# POWER.net
KiCad netlist of a schematic drawn in Altium Designer
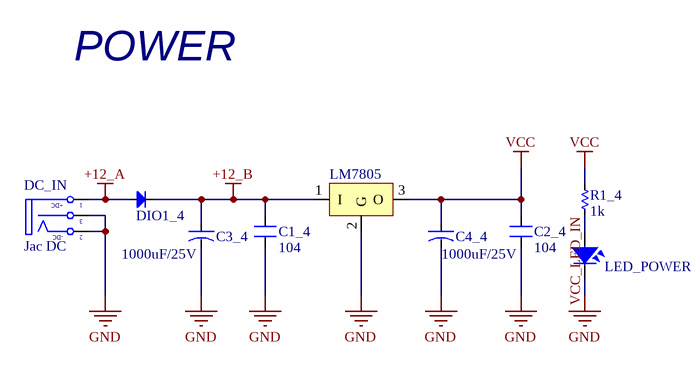
[diagram p0: POWER.SchDoc]

(export (version "E")
  (design (tool "Eeschema 10.0.6"))
  (components
    (comp (ref "C1_4") (value "104") (footprint "CN-SMD-0805") (libsource (lib "Altium Library") (part "CN")))
    (comp (ref "C2_4") (value "104") (footprint "CN-SMD-0805") (libsource (lib "Altium Library") (part "CN")))
    (comp (ref "C3_4")
      (value "1000uF/25V")
      (footprint "CAP-ALU-SMD-4.5x5x1.4")
      (description "Polarized Capacitor (Axial)")
      (fields (field (name "PUBLISHER") "Altium Limited"))
      (libsource (lib "Altium Library") (part "CN-ALU-SMD"))
    )
    (comp (ref "C4_4")
      (value "1000uF/25V")
      (footprint "CAP-ALU-SMD-4.5x5x1.4")
      (description "Polarized Capacitor (Axial)")
      (fields (field (name "PUBLISHER") "Altium Limited"))
      (libsource (lib "Altium Library") (part "CN-ALU-SMD"))
    )
    (comp (ref "DC_IN")
      (value "Jac DC")
      (footprint "DC0")
      (description "Jac DC input")
      (libsource (lib "Altium Library") (part "DCIN"))
    )
    (comp (ref "DIO1_4")
      (value "Diode SMD")
      (footprint "DIO-SMD-106")
      (description "Default Diode")
      (fields (field (name "PUBLISHER") "Altium Limited"))
      (libsource (lib "Altium Library") (part "Diode SMD"))
    )
    (comp (ref "LED_POWER")
      (value "LED")
      (footprint "LED-RED-0805")
      (libsource (lib "Altium Library") (part "LED SMD"))
    )
    (comp (ref "LM7805")
      (value "LM78xx")
      (footprint "TO252-123")
      (description "Positive Voltage Regulator")
      (fields (field (name "PUBLISHER") "Altium Limited"))
      (libsource (lib "Altium Library") (part "LM78xx"))
    )
    (comp (ref "R1_4")
      (value "1k")
      (footprint "RES-SMD-0805")
      (description "Resistor")
      (fields
        (field (name "MANUFACTURER") "Generic Components")
        (field (name "PUBLISHER") "Altium Hobart Technology Centre")
      )
      (libsource (lib "Altium Library") (part "Res-SMD"))
    )
  )
  (nets
    (net (code "1") (name "+12_A") (class "Default")
      (node (ref "DC_IN") (pin "1") (pinfunction "T_1") (pintype "passive"))
      (node (ref "DIO1_4") (pin "1") (pinfunction "A_1") (pintype "passive"))
    )
    (net (code "2") (name "+12_B") (class "Default")
      (node (ref "C1_4") (pin "2") (pinfunction "2_2") (pintype "passive"))
      (node (ref "C3_4") (pin "1") (pinfunction "1_1") (pintype "passive"))
      (node (ref "DIO1_4") (pin "2") (pinfunction "K_2") (pintype "passive"))
      (node (ref "LM7805") (pin "1") (pinfunction "I_1") (pintype "power_in"))
    )
    (net (code "3") (name "/VCC_LED_IN") (class "Default")
      (node (ref "LED_POWER") (pin "1") (pinfunction "1_1") (pintype "passive"))
      (node (ref "R1_4") (pin "2") (pinfunction "2_2") (pintype "passive"))
    )
    (net (code "4") (name "GND") (class "Default")
      (node (ref "C1_4") (pin "1") (pinfunction "1_1") (pintype "passive"))
      (node (ref "C2_4") (pin "1") (pinfunction "1_1") (pintype "passive"))
      (node (ref "C3_4") (pin "2") (pinfunction "2_2") (pintype "passive"))
      (node (ref "C4_4") (pin "2") (pinfunction "2_2") (pintype "passive"))
      (node (ref "DC_IN") (pin "2") (pinfunction "TN_2") (pintype "passive"))
      (node (ref "DC_IN") (pin "3") (pinfunction "S_3") (pintype "power_in"))
      (node (ref "LED_POWER") (pin "2") (pinfunction "2_2") (pintype "passive"))
      (node (ref "LM7805") (pin "2") (pinfunction "G_2") (pintype "power_in"))
    )
    (net (code "5") (name "VCC") (class "Default")
      (node (ref "C2_4") (pin "2") (pinfunction "2_2") (pintype "passive"))
      (node (ref "C4_4") (pin "1") (pinfunction "1_1") (pintype "passive"))
      (node (ref "LM7805") (pin "3") (pinfunction "O_3") (pintype "power_in"))
      (node (ref "R1_4") (pin "1") (pinfunction "1_1") (pintype "passive"))
    )
  )
)
